# SK3000v5_NEW_MOSFETS.net
KiCad netlist of a schematic drawn in EAGLE
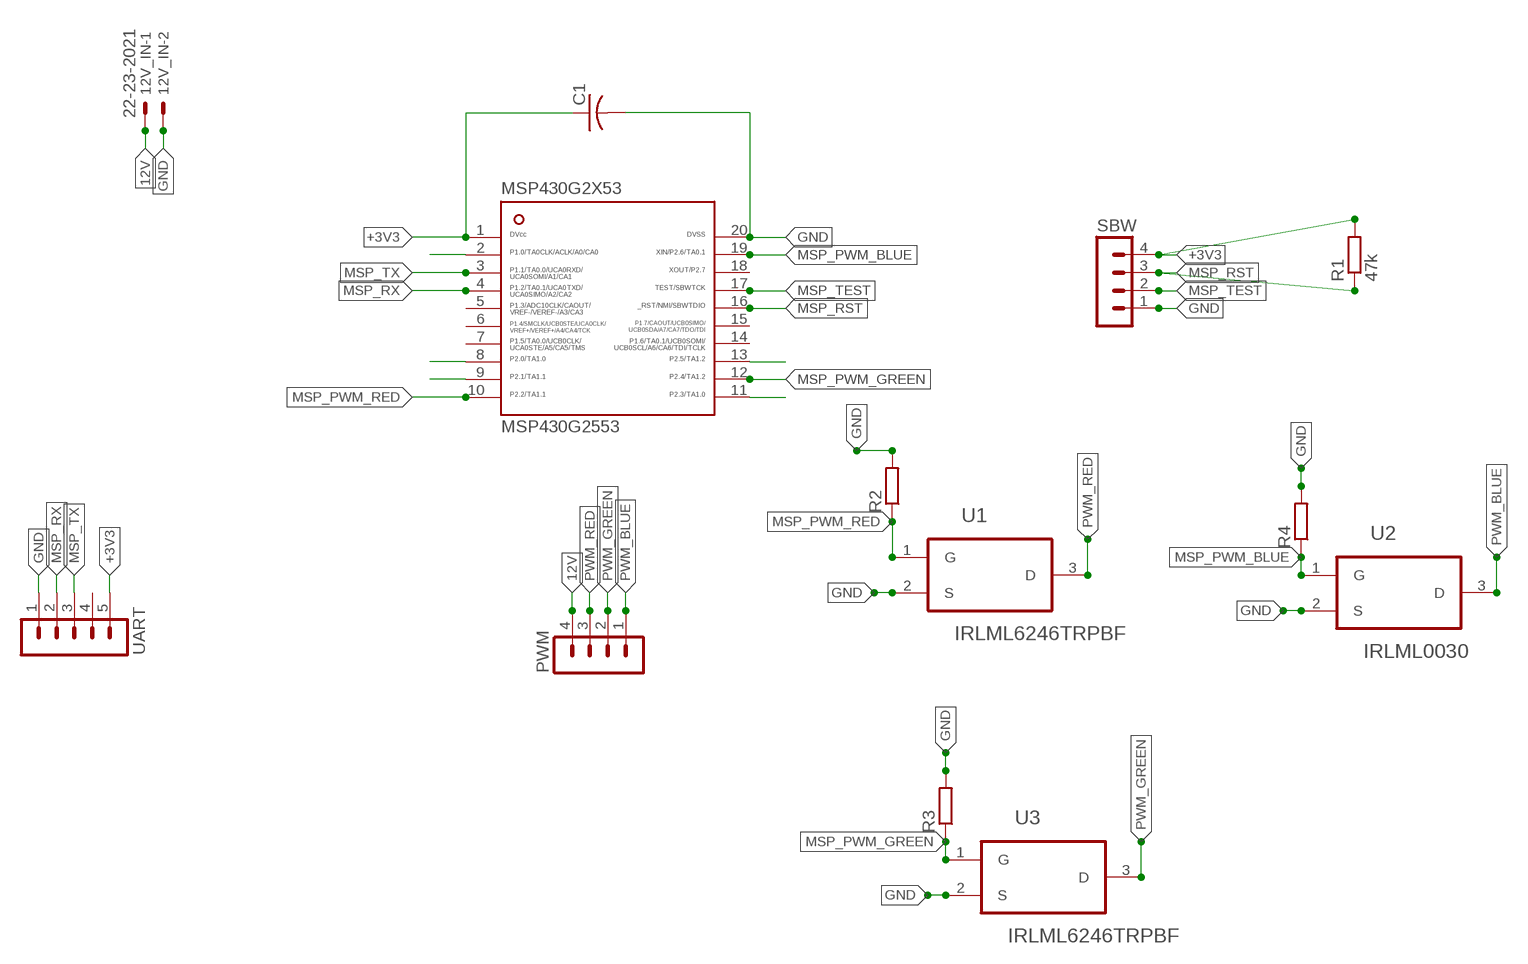
[diagram p0: schematic, sheet 1]

(export (version "E")
  (design (tool "Eeschema 10.0.6"))
  (components
    (comp (ref "12V_IN")
      (value "22-23-2021")
      (footprint "eagle-import:22-23-2021")
      (fields (field (name "MF") "MOLEX"))
      (libsource (lib "eagle-import") (part "22-23-2021"))
    )
    (comp (ref "C1")
      (value "C-USC0603")
      (footprint "eagle-import:C0603")
      (libsource (lib "eagle-import") (part "C-USC0603"))
    )
    (comp (ref "MSP430G2553")
      (value "MSP430G2X53-20PW20")
      (footprint "eagle-import:PW20")
      (libsource (lib "eagle-import") (part "MSP430G2X53-20PW20"))
    )
    (comp (ref "PWM")
      (value "MA04-1")
      (footprint "eagle-import:MA04-1")
      (libsource (lib "eagle-import") (part "MA04-1"))
    )
    (comp (ref "R1")
      (value "47k")
      (footprint "eagle-import:R0603")
      (libsource (lib "eagle-import") (part "R-EU_R0603"))
    )
    (comp (ref "R2")
      (value "R-EU_R0603")
      (footprint "eagle-import:R0603")
      (libsource (lib "eagle-import") (part "R-EU_R0603"))
    )
    (comp (ref "R3")
      (value "R-EU_R0603")
      (footprint "eagle-import:R0603")
      (libsource (lib "eagle-import") (part "R-EU_R0603"))
    )
    (comp (ref "R4")
      (value "R-EU_R0603")
      (footprint "eagle-import:R0603")
      (libsource (lib "eagle-import") (part "R-EU_R0603"))
    )
    (comp (ref "SBW")
      (value "MA04-1")
      (footprint "eagle-import:MA04-1")
      (libsource (lib "eagle-import") (part "MA04-1"))
    )
    (comp (ref "U1")
      (value "IRLML6246TRPBF")
      (footprint "eagle-import:SOT95P240X112-3N")
      (libsource (lib "eagle-import") (part "IRLML6246TRPBF"))
    )
    (comp (ref "U2")
      (value "IRLML0030")
      (footprint "eagle-import:SOT95P240X112-3N")
      (fields (field (name "MPN") "IRLML6246TRPBF"))
      (libsource (lib "eagle-import") (part "IRLML6246TRPBF"))
    )
    (comp (ref "U3")
      (value "IRLML6246TRPBF")
      (footprint "eagle-import:SOT95P240X112-3N")
      (libsource (lib "eagle-import") (part "IRLML6246TRPBF"))
    )
    (comp (ref "UART")
      (value "MA05-1")
      (footprint "eagle-import:MA05-1")
      (libsource (lib "eagle-import") (part "MA05-1"))
    )
  )
  (nets
    (net (code "1") (name "+3V3") (class "Default")
      (node (ref "C1") (pin "1") (pinfunction "1_1") (pintype "passive"))
      (node (ref "MSP430G2553") (pin "1") (pinfunction "1_1") (pintype "bidirectional"))
      (node (ref "R1") (pin "2") (pinfunction "2_2") (pintype "passive"))
      (node (ref "SBW") (pin "4") (pinfunction "4_4") (pintype "passive"))
      (node (ref "UART") (pin "5") (pinfunction "5_5") (pintype "passive"))
    )
    (net (code "2") (name "12V") (class "Default")
      (node (ref "12V_IN") (pin "1") (pinfunction "S_1") (pintype "passive"))
      (node (ref "PWM") (pin "4") (pinfunction "4_4") (pintype "passive"))
    )
    (net (code "3") (name "GND") (class "Default")
      (node (ref "12V_IN") (pin "2") (pinfunction "S_2") (pintype "passive"))
      (node (ref "C1") (pin "2") (pinfunction "2_2") (pintype "passive"))
      (node (ref "MSP430G2553") (pin "20") (pinfunction "20_20") (pintype "bidirectional"))
      (node (ref "R2") (pin "2") (pinfunction "2_2") (pintype "passive"))
      (node (ref "R3") (pin "2") (pinfunction "2_2") (pintype "passive"))
      (node (ref "R4") (pin "2") (pinfunction "2_2") (pintype "passive"))
      (node (ref "SBW") (pin "1") (pinfunction "1_1") (pintype "passive"))
      (node (ref "U1") (pin "2") (pinfunction "S_2") (pintype "passive"))
      (node (ref "U2") (pin "2") (pinfunction "S_2") (pintype "passive"))
      (node (ref "U3") (pin "2") (pinfunction "S_2") (pintype "passive"))
      (node (ref "UART") (pin "1") (pinfunction "1_1") (pintype "passive"))
    )
    (net (code "4") (name "MSP_PWM_BLUE") (class "Default")
      (node (ref "MSP430G2553") (pin "19") (pinfunction "19_19") (pintype "bidirectional"))
      (node (ref "R4") (pin "1") (pinfunction "1_1") (pintype "passive"))
      (node (ref "U2") (pin "1") (pinfunction "G_1") (pintype "input"))
    )
    (net (code "5") (name "MSP_PWM_GREEN") (class "Default")
      (node (ref "MSP430G2553") (pin "12") (pinfunction "12_12") (pintype "bidirectional"))
      (node (ref "R3") (pin "1") (pinfunction "1_1") (pintype "passive"))
      (node (ref "U3") (pin "1") (pinfunction "G_1") (pintype "input"))
    )
    (net (code "6") (name "MSP_PWM_RED") (class "Default")
      (node (ref "MSP430G2553") (pin "10") (pinfunction "10_10") (pintype "bidirectional"))
      (node (ref "R2") (pin "1") (pinfunction "1_1") (pintype "passive"))
      (node (ref "U1") (pin "1") (pinfunction "G_1") (pintype "input"))
    )
    (net (code "7") (name "MSP_RST") (class "Default")
      (node (ref "MSP430G2553") (pin "16") (pinfunction "16_16") (pintype "bidirectional"))
      (node (ref "R1") (pin "1") (pinfunction "1_1") (pintype "passive"))
      (node (ref "SBW") (pin "3") (pinfunction "3_3") (pintype "passive"))
    )
    (net (code "8") (name "MSP_RX") (class "Default")
      (node (ref "MSP430G2553") (pin "4") (pinfunction "4_4") (pintype "bidirectional"))
      (node (ref "UART") (pin "2") (pinfunction "2_2") (pintype "passive"))
    )
    (net (code "9") (name "MSP_TEST") (class "Default")
      (node (ref "MSP430G2553") (pin "17") (pinfunction "17_17") (pintype "bidirectional"))
      (node (ref "SBW") (pin "2") (pinfunction "2_2") (pintype "passive"))
    )
    (net (code "10") (name "MSP_TX") (class "Default")
      (node (ref "MSP430G2553") (pin "3") (pinfunction "3_3") (pintype "bidirectional"))
      (node (ref "UART") (pin "3") (pinfunction "3_3") (pintype "passive"))
    )
    (net (code "11") (name "PWM_BLUE") (class "Default")
      (node (ref "PWM") (pin "1") (pinfunction "1_1") (pintype "passive"))
      (node (ref "U2") (pin "3") (pinfunction "D_3") (pintype "output"))
    )
    (net (code "12") (name "PWM_GREEN") (class "Default")
      (node (ref "PWM") (pin "2") (pinfunction "2_2") (pintype "passive"))
      (node (ref "U3") (pin "3") (pinfunction "D_3") (pintype "output"))
    )
    (net (code "13") (name "PWM_RED") (class "Default")
      (node (ref "PWM") (pin "3") (pinfunction "3_3") (pintype "passive"))
      (node (ref "U1") (pin "3") (pinfunction "D_3") (pintype "output"))
    )
    (net (code "14") (name "unconnected-(MSP430G2553-Pad2)") (class "Default")
      (node (ref "MSP430G2553") (pin "2") (pinfunction "2_2") (pintype "bidirectional"))
    )
    (net (code "15") (name "unconnected-(MSP430G2553-Pad5)") (class "Default")
      (node (ref "MSP430G2553") (pin "5") (pinfunction "5_5") (pintype "bidirectional"))
    )
    (net (code "16") (name "unconnected-(MSP430G2553-Pad6)") (class "Default")
      (node (ref "MSP430G2553") (pin "6") (pinfunction "6_6") (pintype "bidirectional"))
    )
    (net (code "17") (name "unconnected-(MSP430G2553-Pad7)") (class "Default")
      (node (ref "MSP430G2553") (pin "7") (pinfunction "7_7") (pintype "bidirectional"))
    )
    (net (code "18") (name "unconnected-(MSP430G2553-Pad8)") (class "Default")
      (node (ref "MSP430G2553") (pin "8") (pinfunction "8_8") (pintype "bidirectional"))
    )
    (net (code "19") (name "unconnected-(MSP430G2553-Pad9)") (class "Default")
      (node (ref "MSP430G2553") (pin "9") (pinfunction "9_9") (pintype "bidirectional"))
    )
    (net (code "20") (name "unconnected-(MSP430G2553-Pad11)") (class "Default")
      (node (ref "MSP430G2553") (pin "11") (pinfunction "11_11") (pintype "bidirectional"))
    )
    (net (code "21") (name "unconnected-(MSP430G2553-Pad13)") (class "Default")
      (node (ref "MSP430G2553") (pin "13") (pinfunction "13_13") (pintype "bidirectional"))
    )
    (net (code "22") (name "unconnected-(MSP430G2553-Pad14)") (class "Default")
      (node (ref "MSP430G2553") (pin "14") (pinfunction "14_14") (pintype "bidirectional"))
    )
    (net (code "23") (name "unconnected-(MSP430G2553-Pad15)") (class "Default")
      (node (ref "MSP430G2553") (pin "15") (pinfunction "15_15") (pintype "bidirectional"))
    )
    (net (code "24") (name "unconnected-(MSP430G2553-Pad18)") (class "Default")
      (node (ref "MSP430G2553") (pin "18") (pinfunction "18_18") (pintype "bidirectional"))
    )
    (net (code "25") (name "unconnected-(UART-Pad4)") (class "Default")
      (node (ref "UART") (pin "4") (pinfunction "4_4") (pintype "passive"))
    )
  )
)
